# SHDN21-S01-V00-Shutdown.net
KiCad netlist of a schematic drawn in Altium Designer
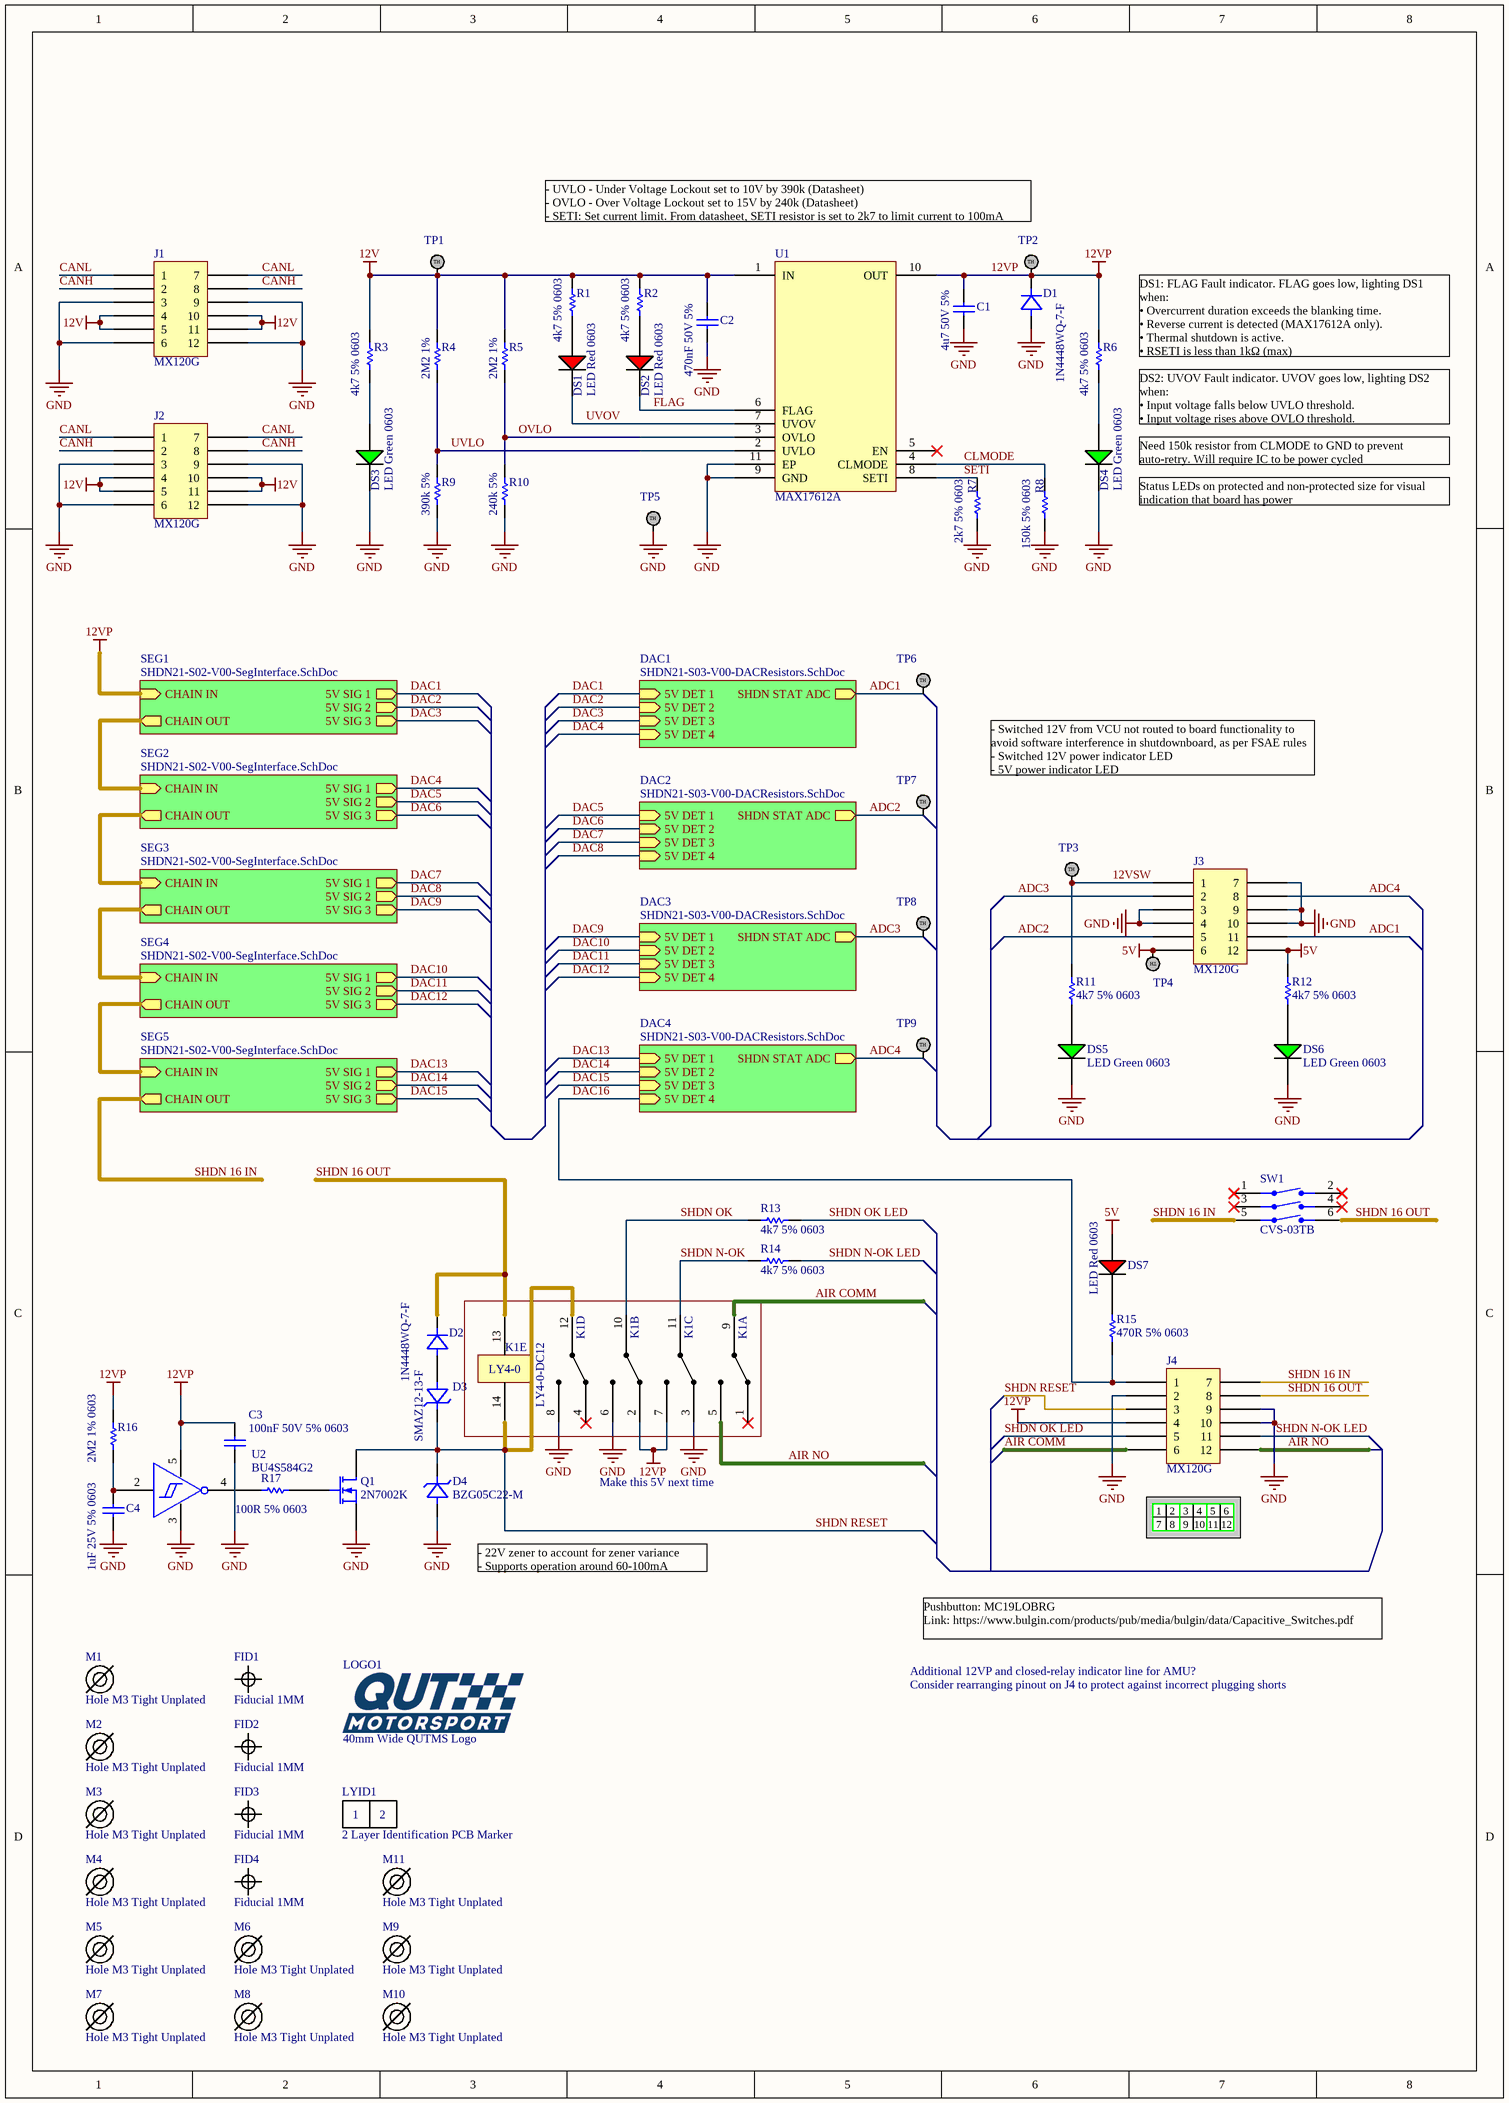
[diagram p0: SHDN21-S01-V00-Shutdown.SchDoc]

(export (version "E")
  (design (tool "Eeschema 10.0.6"))
  (components
    (comp (ref "C1")
      (value "4u7 50V 5%")
      (footprint "Cap_Ceramic_0603")
      (description "Capacitor, Ceramic, SMD, 4u7, 50V, 5%, X7R, 0603")
      (libsource (lib "StandardCapacitors") (part "4u7 50V 5% X7R 0603"))
    )
    (comp (ref "C2")
      (value "470nF 50V 5%")
      (footprint "Cap_Ceramic_0603")
      (description "Capacitor, Ceramic, SMD, 470nF, 50V, 5%, X7R, 0603")
      (libsource (lib "StandardCapacitors") (part "470nF 50V 5% X7R 0603"))
    )
    (comp (ref "C3")
      (value "100nF 50V 5% 0603")
      (footprint "Cap_Ceramic_0603")
      (description "Capacitor, Ceramic, SMD, 100nF, 50V, 5%, X7R, 0603")
      (libsource (lib "StandardCapacitors") (part "100nF 50V 5% X7R 0603"))
    )
    (comp (ref "C4")
      (value "1uF 25V 5% 0603")
      (footprint "Cap_Ceramic_0603")
      (description "Capacitor, Ceramic, SMD, 1uF, 25V, 5%, X7R, 0603")
      (libsource (lib "StandardCapacitors") (part "1uF 25V 5% X7R 0603"))
    )
    (comp (ref "D1")
      (value "1N4448WQ-7-F")
      (footprint "SMA")
      (description "Diode, SMD, 75V, 5%, 250mA, SOD123")
      (fields
        (field (name "MANUFACTURER") "ON Semiconductor / Fairchild")
        (field (name "MANUFACTURER PART NUMBER") "1N914BWS")
      )
      (libsource (lib "QUTMS_DiodeLibrary") (part "1N4448WQ-7-F"))
    )
    (comp (ref "D2")
      (value "1N4448WQ-7-F")
      (footprint "SMA")
      (description "Diode, SMD, 75V, 5%, 250mA, SOD123")
      (fields
        (field (name "MANUFACTURER") "ON Semiconductor / Fairchild")
        (field (name "MANUFACTURER PART NUMBER") "1N914BWS")
      )
      (libsource (lib "QUTMS_DiodeLibrary") (part "1N4448WQ-7-F"))
    )
    (comp (ref "D3")
      (value "SMAZ12-13-F")
      (footprint "SMA")
      (description "Zener Diode 12V 1W ±5% Surface Mount SMA")
      (fields (field (name "MANUFACTURER") "ON Semiconductor") (field (name "MPN") "MM3Z56VB"))
      (libsource (lib "QUTMS_DiodeLibrary") (part "SMAZ12-13-F"))
    )
    (comp (ref "D4")
      (value "BZG05C22-M")
      (footprint "SMA")
      (description "Zener Diodes Uni-direc 40W Pppm SMA (DO-214AC)")
      (libsource (lib "QUTMS_DiodeLibrary") (part "BZG05C22-M"))
    )
    (comp (ref "DS1")
      (value "LED Red 0603")
      (footprint "LED RED 0603")
      (libsource (lib "QUTMS_LEDLibrary") (part "LED Red 0603"))
    )
    (comp (ref "DS2")
      (value "LED Red 0603")
      (footprint "LED RED 0603")
      (libsource (lib "QUTMS_LEDLibrary") (part "LED Red 0603"))
    )
    (comp (ref "DS3")
      (value "LED Green 0603")
      (footprint "LED GREEN 0603")
      (libsource (lib "QUTMS_LEDLibrary") (part "LED Green 0603"))
    )
    (comp (ref "DS4")
      (value "LED Green 0603")
      (footprint "LED GREEN 0603")
      (libsource (lib "QUTMS_LEDLibrary") (part "LED Green 0603"))
    )
    (comp (ref "DS5")
      (value "LED Green 0603")
      (footprint "LED GREEN 0603")
      (libsource (lib "QUTMS_LEDLibrary") (part "LED Green 0603"))
    )
    (comp (ref "DS6")
      (value "LED Green 0603")
      (footprint "LED GREEN 0603")
      (libsource (lib "QUTMS_LEDLibrary") (part "LED Green 0603"))
    )
    (comp (ref "DS7")
      (value "LED Red 0603")
      (footprint "LED RED 0603")
      (libsource (lib "QUTMS_LEDLibrary") (part "LED Red 0603"))
    )
    (comp (ref "FID1")
      (value "Fiducial 1MM")
      (footprint "FIDUCIAL 1MM")
      (libsource (lib "QUTMS_PCBLibrary") (part "Fiducial 1MM"))
    )
    (comp (ref "FID2")
      (value "Fiducial 1MM")
      (footprint "FIDUCIAL 1MM")
      (libsource (lib "QUTMS_PCBLibrary") (part "Fiducial 1MM"))
    )
    (comp (ref "FID3")
      (value "Fiducial 1MM")
      (footprint "FIDUCIAL 1MM")
      (libsource (lib "QUTMS_PCBLibrary") (part "Fiducial 1MM"))
    )
    (comp (ref "FID4")
      (value "Fiducial 1MM")
      (footprint "FIDUCIAL 1MM")
      (libsource (lib "QUTMS_PCBLibrary") (part "Fiducial 1MM"))
    )
    (comp (ref "J1")
      (value "MX120G")
      (footprint "MX120G")
      (description "MX120G with standard connector layout")
      (libsource (lib "QUTMS_MolexLibrary") (part "MX120G"))
    )
    (comp (ref "J2")
      (value "MX120G")
      (footprint "MX120G")
      (description "MX120G with standard connector layout")
      (libsource (lib "QUTMS_MolexLibrary") (part "MX120G"))
    )
    (comp (ref "J3")
      (value "MX120G")
      (footprint "MX120G")
      (description "MX120G with standard connector layout")
      (libsource (lib "QUTMS_MolexLibrary") (part "MX120G"))
    )
    (comp (ref "J4")
      (value "MX120G")
      (footprint "MX120G")
      (description "MX120G with standard connector layout")
      (libsource (lib "QUTMS_MolexLibrary") (part "MX120G"))
    )
    (comp (ref "K1")
      (value "LY4-0-DC12")
      (footprint "LY4-0-DC12")
      (description "RELAY GEN PURPOSE 4PDT 10A 12V Through-hole")
      (libsource (lib "QUTMS_RelayLibrary") (part "LY4-0-DC12_Parts"))
    )
    (comp (ref "LOGO1")
      (value "40mm Wide QUTMS Logo")
      (footprint "QUTMS LOGO 40MM")
      (libsource (lib "QUTMS_PCBLibrary") (part "QUTMS Logo 40mm"))
    )
    (comp (ref "LYID1")
      (value "2 Layer Identification PCB Marker")
      (footprint "LAYER IDENT 2")
      (libsource (lib "QUTMS_PCBLibrary") (part "Layer Identification 2"))
    )
    (comp (ref "M1")
      (value "Hole M3 Tight Unplated")
      (footprint "M3.2 UNPLATED")
      (description "M3.2 Hole, No Plating")
      (libsource (lib "QUTMS_PCBLibrary") (part "Hole M3 Tight Unplated"))
    )
    (comp (ref "M2")
      (value "Hole M3 Tight Unplated")
      (footprint "M3.2 UNPLATED")
      (description "M3.2 Hole, No Plating")
      (libsource (lib "QUTMS_PCBLibrary") (part "Hole M3 Tight Unplated"))
    )
    (comp (ref "M3")
      (value "Hole M3 Tight Unplated")
      (footprint "M3.2 UNPLATED")
      (description "M3.2 Hole, No Plating")
      (libsource (lib "QUTMS_PCBLibrary") (part "Hole M3 Tight Unplated"))
    )
    (comp (ref "M4")
      (value "Hole M3 Tight Unplated")
      (footprint "M3.2 UNPLATED")
      (description "M3.2 Hole, No Plating")
      (libsource (lib "QUTMS_PCBLibrary") (part "Hole M3 Tight Unplated"))
    )
    (comp (ref "M5")
      (value "Hole M3 Tight Unplated")
      (footprint "M3.2 UNPLATED")
      (description "M3.2 Hole, No Plating")
      (libsource (lib "QUTMS_PCBLibrary") (part "Hole M3 Tight Unplated"))
    )
    (comp (ref "M6")
      (value "Hole M3 Tight Unplated")
      (footprint "M3.2 UNPLATED")
      (description "M3.2 Hole, No Plating")
      (libsource (lib "QUTMS_PCBLibrary") (part "Hole M3 Tight Unplated"))
    )
    (comp (ref "M7")
      (value "Hole M3 Tight Unplated")
      (footprint "M3.2 UNPLATED")
      (description "M3.2 Hole, No Plating")
      (libsource (lib "QUTMS_PCBLibrary") (part "Hole M3 Tight Unplated"))
    )
    (comp (ref "M8")
      (value "Hole M3 Tight Unplated")
      (footprint "M3.2 UNPLATED")
      (description "M3.2 Hole, No Plating")
      (libsource (lib "QUTMS_PCBLibrary") (part "Hole M3 Tight Unplated"))
    )
    (comp (ref "M9")
      (value "Hole M3 Tight Unplated")
      (footprint "M3.2 UNPLATED")
      (description "M3.2 Hole, No Plating")
      (libsource (lib "QUTMS_PCBLibrary") (part "Hole M3 Tight Unplated"))
    )
    (comp (ref "M10")
      (value "Hole M3 Tight Unplated")
      (footprint "M3.2 UNPLATED")
      (description "M3.2 Hole, No Plating")
      (libsource (lib "QUTMS_PCBLibrary") (part "Hole M3 Tight Unplated"))
    )
    (comp (ref "M11")
      (value "Hole M3 Tight Unplated")
      (footprint "M3.2 UNPLATED")
      (description "M3.2 Hole, No Plating")
      (libsource (lib "QUTMS_PCBLibrary") (part "Hole M3 Tight Unplated"))
    )
    (comp (ref "Q1")
      (value "2N7002K")
      (footprint "SOT-23-3")
      (description "N-Channel 60V 300mA (Ta) 350mW (Ta) Surface Mount SOT-23 (TO-236AB)")
      (libsource (lib "QUTMS_Transistors") (part "2N7002K"))
    )
    (comp (ref "R1")
      (value "4k7 5% 0603")
      (footprint "Res_ThinFilm_0603")
      (description "Resistor, SMD, 4k7, 0.1W, 5%, 0603")
      (libsource (lib "StandardResistors") (part "4k7 5% 0603"))
    )
    (comp (ref "R2")
      (value "4k7 5% 0603")
      (footprint "Res_ThinFilm_0603")
      (description "Resistor, SMD, 4k7, 0.1W, 5%, 0603")
      (libsource (lib "StandardResistors") (part "4k7 5% 0603"))
    )
    (comp (ref "R3")
      (value "4k7 5% 0603")
      (footprint "Res_ThinFilm_0603")
      (description "Resistor, SMD, 4k7, 0.1W, 5%, 0603")
      (libsource (lib "StandardResistors") (part "4k7 5% 0603"))
    )
    (comp (ref "R4")
      (value "2M2 1%")
      (footprint "Res_ThinFilm_0603")
      (description "Resistor, SMD, 2M2, 0.125W, 1%, 0603")
      (libsource (lib "StandardResistors") (part "2M2 1% 0603"))
    )
    (comp (ref "R5")
      (value "2M2 1%")
      (footprint "Res_ThinFilm_0603")
      (description "Resistor, SMD, 2M2, 0.125W, 1%, 0603")
      (libsource (lib "StandardResistors") (part "2M2 1% 0603"))
    )
    (comp (ref "R6")
      (value "4k7 5% 0603")
      (footprint "Res_ThinFilm_0603")
      (description "Resistor, SMD, 4k7, 0.1W, 5%, 0603")
      (libsource (lib "StandardResistors") (part "4k7 5% 0603"))
    )
    (comp (ref "R7")
      (value "2k7 5% 0603")
      (footprint "Res_ThinFilm_0603")
      (description "Resistor, SMD, 2k7, 0.1W, 5%, 0603")
      (libsource (lib "StandardResistors") (part "2k7 5% 0603"))
    )
    (comp (ref "R8")
      (value "150k 5% 0603")
      (footprint "Res_ThinFilm_0603")
      (description "Resistor, SMD, 150k, 0.1W, 5%, 0603")
      (libsource (lib "StandardResistors") (part "150k 5%, 0603"))
    )
    (comp (ref "R9")
      (value "390k 5%")
      (footprint "Res_ThinFilm_0603")
      (description "Resistor, SMD, 390k, 0.1W, 5%, 0603")
      (libsource (lib "StandardResistors") (part "390k 5% 0603"))
    )
    (comp (ref "R10")
      (value "240k 5%")
      (footprint "Res_ThinFilm_0603")
      (description "Resistor, SMD, 240k, 0.1W, 5%, 0603")
      (libsource (lib "StandardResistors") (part "240k 5% 0603"))
    )
    (comp (ref "R11")
      (value "4k7 5% 0603")
      (footprint "Res_ThinFilm_0603")
      (description "Resistor, SMD, 4k7, 0.1W, 5%, 0603")
      (libsource (lib "StandardResistors") (part "4k7 5% 0603"))
    )
    (comp (ref "R12")
      (value "4k7 5% 0603")
      (footprint "Res_ThinFilm_0603")
      (description "Resistor, SMD, 4k7, 0.1W, 5%, 0603")
      (libsource (lib "StandardResistors") (part "4k7 5% 0603"))
    )
    (comp (ref "R13")
      (value "4k7 5% 0603")
      (footprint "Res_ThinFilm_0603")
      (description "Resistor, SMD, 4k7, 0.1W, 5%, 0603")
      (libsource (lib "StandardResistors") (part "4k7 5% 0603"))
    )
    (comp (ref "R14")
      (value "4k7 5% 0603")
      (footprint "Res_ThinFilm_0603")
      (description "Resistor, SMD, 4k7, 0.1W, 5%, 0603")
      (libsource (lib "StandardResistors") (part "4k7 5% 0603"))
    )
    (comp (ref "R15")
      (value "470R 5% 0603")
      (footprint "Res_ThinFilm_0603")
      (description "Resistor, SMD, 470R, 0.1W, 5%, 0603")
      (libsource (lib "StandardResistors") (part "470R 5% 0603"))
    )
    (comp (ref "R16")
      (value "2M2 1% 0603")
      (footprint "Res_ThinFilm_0603")
      (description "Resistor, SMD, 2M2, 0.125W, 1%, 0603")
      (libsource (lib "StandardResistors") (part "2M2 1% 0603"))
    )
    (comp (ref "R17")
      (value "100R 5% 0603")
      (footprint "Res_ThinFilm_0603")
      (description "Resistor, SMD, 100R, 0.1W, 5%, 0603")
      (libsource (lib "StandardResistors") (part "100R 5%, 0603"))
    )
    (comp (ref "SW1")
      (value "CVS-03TB")
      (footprint "CVS-03TB")
      (description "SWITCH SLIDE DIP SPST 100MA 6V")
      (libsource (lib "QUTMS_SwitchLibrary") (part "CVS-03TB"))
    )
    (comp (ref "TP1")
      (value "TestPoint")
      (footprint "TestPoint")
      (libsource (lib "StandardTest") (part "TestPoint"))
    )
    (comp (ref "TP2")
      (value "TestPoint")
      (footprint "TestPoint")
      (libsource (lib "StandardTest") (part "TestPoint"))
    )
    (comp (ref "TP3")
      (value "TestPoint")
      (footprint "TestPoint")
      (libsource (lib "StandardTest") (part "TestPoint"))
    )
    (comp (ref "TP4")
      (value "TestPoint")
      (footprint "TestPoint")
      (libsource (lib "StandardTest") (part "TestPoint"))
    )
    (comp (ref "TP5")
      (value "TestPoint")
      (footprint "TestPoint")
      (libsource (lib "StandardTest") (part "TestPoint"))
    )
    (comp (ref "TP6")
      (value "TestPoint")
      (footprint "TestPoint")
      (libsource (lib "StandardTest") (part "TestPoint"))
    )
    (comp (ref "TP7")
      (value "TestPoint")
      (footprint "TestPoint")
      (libsource (lib "StandardTest") (part "TestPoint"))
    )
    (comp (ref "TP8")
      (value "TestPoint")
      (footprint "TestPoint")
      (libsource (lib "StandardTest") (part "TestPoint"))
    )
    (comp (ref "TP9")
      (value "TestPoint")
      (footprint "TestPoint")
      (libsource (lib "StandardTest") (part "TestPoint"))
    )
    (comp (ref "U1")
      (value "MAX17612A")
      (footprint "10-Pin TDFN EP")
      (libsource (lib "QUTMS_IntegratedCircuitLibrary") (part "MAX17612A"))
    )
    (comp (ref "U2")
      (value "BU4S584G2")
      (footprint "SSOP5")
      (description "IC INVERTER SCHMITT 1CH 5SSOP")
      (libsource (lib "QUTMS_LogicLibrary") (part "BU4S584G2"))
    )
  )
  (nets
    (net (code "1") (name "/12VSW") (class "Default")
      (node (ref "J3") (pin "1") (pinfunction "1_1") (pintype "passive"))
      (node (ref "R11") (pin "2") (pinfunction "2_2") (pintype "passive"))
      (node (ref "TP3") (pin "1") (pinfunction "1_1") (pintype "passive"))
    )
    (net (code "2") (name "/ADC1") (class "Default")
      (node (ref "J3") (pin "11") (pinfunction "11_11") (pintype "passive"))
      (node (ref "TP6") (pin "1") (pinfunction "1_1") (pintype "passive"))
    )
    (net (code "3") (name "/ADC2") (class "Default")
      (node (ref "J3") (pin "5") (pinfunction "5_5") (pintype "passive"))
      (node (ref "TP7") (pin "1") (pinfunction "1_1") (pintype "passive"))
    )
    (net (code "4") (name "/ADC3") (class "Default")
      (node (ref "J3") (pin "2") (pinfunction "2_2") (pintype "passive"))
      (node (ref "TP8") (pin "1") (pinfunction "1_1") (pintype "passive"))
    )
    (net (code "5") (name "/ADC4") (class "Default")
      (node (ref "J3") (pin "8") (pinfunction "8_8") (pintype "passive"))
      (node (ref "TP9") (pin "1") (pinfunction "1_1") (pintype "passive"))
    )
    (net (code "6") (name "/AIR COMM") (class "Default")
      (node (ref "J4") (pin "6") (pinfunction "6_6") (pintype "passive"))
      (node (ref "K1") (pin "9") (pinfunction "9_9") (pintype "passive"))
    )
    (net (code "7") (name "/AIR NO") (class "Default")
      (node (ref "J4") (pin "12") (pinfunction "12_12") (pintype "passive"))
      (node (ref "K1") (pin "5") (pinfunction "5_5") (pintype "passive"))
    )
    (net (code "8") (name "/CANH") (class "Default")
      (node (ref "J1") (pin "2") (pinfunction "2_2") (pintype "passive"))
      (node (ref "J1") (pin "8") (pinfunction "8_8") (pintype "passive"))
      (node (ref "J2") (pin "2") (pinfunction "2_2") (pintype "passive"))
      (node (ref "J2") (pin "8") (pinfunction "8_8") (pintype "passive"))
    )
    (net (code "9") (name "/CANL") (class "Default")
      (node (ref "J1") (pin "1") (pinfunction "1_1") (pintype "passive"))
      (node (ref "J1") (pin "7") (pinfunction "7_7") (pintype "passive"))
      (node (ref "J2") (pin "1") (pinfunction "1_1") (pintype "passive"))
      (node (ref "J2") (pin "7") (pinfunction "7_7") (pintype "passive"))
    )
    (net (code "14") (name "/CLMODE") (class "Default")
      (node (ref "R8") (pin "2") (pinfunction "2_2") (pintype "passive"))
      (node (ref "U1") (pin "4") (pinfunction "CLMODE_4") (pintype "passive"))
    )
    (net (code "30") (name "/DAC16") (class "Default")
      (node (ref "J4") (pin "1") (pinfunction "1_1") (pintype "passive"))
      (node (ref "R15") (pin "1") (pinfunction "1_1") (pintype "passive"))
    )
    (net (code "31") (name "/FLAG") (class "Default")
      (node (ref "DS2") (pin "2") (pinfunction "C_2") (pintype "passive"))
      (node (ref "U1") (pin "6") (pinfunction "FLAG_6") (pintype "passive"))
    )
    (net (code "32") (name "/OVLO") (class "Default")
      (node (ref "R10") (pin "2") (pinfunction "2_2") (pintype "passive"))
      (node (ref "R5") (pin "1") (pinfunction "1_1") (pintype "passive"))
      (node (ref "U1") (pin "3") (pinfunction "OVLO_3") (pintype "passive"))
    )
    (net (code "33") (name "/SETI") (class "Default")
      (node (ref "R7") (pin "1") (pinfunction "1_1") (pintype "passive"))
      (node (ref "U1") (pin "8") (pinfunction "SETI_8") (pintype "passive"))
    )
    (net (code "34") (name "/SHDN 16 IN") (class "Default")
      (node (ref "J4") (pin "7") (pinfunction "7_7") (pintype "passive"))
      (node (ref "SW1") (pin "5") (pinfunction "5_5") (pintype "passive"))
    )
    (net (code "35") (name "/SHDN 16 OUT") (class "Default")
      (node (ref "D2") (pin "K") (pinfunction "Cathode_K") (pintype "passive"))
      (node (ref "J4") (pin "8") (pinfunction "8_8") (pintype "passive"))
      (node (ref "K1") (pin "13") (pinfunction "13_13") (pintype "passive"))
      (node (ref "SW1") (pin "6") (pinfunction "6_6") (pintype "passive"))
    )
    (net (code "36") (name "/SHDN N-OK") (class "Default")
      (node (ref "K1") (pin "11") (pinfunction "11_11") (pintype "passive"))
      (node (ref "R14") (pin "1") (pinfunction "1_1") (pintype "passive"))
    )
    (net (code "37") (name "/SHDN N-OK LED") (class "Default")
      (node (ref "J4") (pin "11") (pinfunction "11_11") (pintype "passive"))
      (node (ref "R14") (pin "2") (pinfunction "2_2") (pintype "passive"))
    )
    (net (code "38") (name "/SHDN OK") (class "Default")
      (node (ref "K1") (pin "10") (pinfunction "10_10") (pintype "passive"))
      (node (ref "R13") (pin "1") (pinfunction "1_1") (pintype "passive"))
    )
    (net (code "39") (name "/SHDN OK LED") (class "Default")
      (node (ref "J4") (pin "5") (pinfunction "5_5") (pintype "passive"))
      (node (ref "R13") (pin "2") (pinfunction "2_2") (pintype "passive"))
    )
    (net (code "40") (name "/SHDN RESET") (class "Default")
      (node (ref "D3") (pin "K") (pinfunction "Cathode_K") (pintype "passive"))
      (node (ref "D4") (pin "K") (pinfunction "Cathode_K") (pintype "passive"))
      (node (ref "J4") (pin "3") (pinfunction "3_3") (pintype "passive"))
      (node (ref "K1") (pin "12") (pinfunction "12_12") (pintype "passive"))
      (node (ref "K1") (pin "14") (pinfunction "14_14") (pintype "passive"))
      (node (ref "Q1") (pin "D") (pinfunction "D_D") (pintype "passive"))
    )
    (net (code "41") (name "/UVLO") (class "Default")
      (node (ref "R4") (pin "1") (pinfunction "1_1") (pintype "passive"))
      (node (ref "R9") (pin "2") (pinfunction "2_2") (pintype "passive"))
      (node (ref "U1") (pin "2") (pinfunction "UVLO_2") (pintype "passive"))
    )
    (net (code "42") (name "/UVOV") (class "Default")
      (node (ref "DS1") (pin "2") (pinfunction "C_2") (pintype "passive"))
      (node (ref "U1") (pin "7") (pinfunction "UVOV_7") (pintype "passive"))
    )
    (net (code "43") (name "5V") (class "Default")
      (node (ref "DS7") (pin "1") (pinfunction "A_1") (pintype "passive"))
      (node (ref "J3") (pin "12") (pinfunction "12_12") (pintype "passive"))
      (node (ref "J3") (pin "6") (pinfunction "6_6") (pintype "passive"))
      (node (ref "R12") (pin "2") (pinfunction "2_2") (pintype "passive"))
      (node (ref "TP4") (pin "1") (pinfunction "1_1") (pintype "passive"))
    )
    (net (code "44") (name "12V") (class "Default")
      (node (ref "C2") (pin "2") (pinfunction "2_2") (pintype "passive"))
      (node (ref "J1") (pin "10") (pinfunction "10_10") (pintype "passive"))
      (node (ref "J1") (pin "11") (pinfunction "11_11") (pintype "passive"))
      (node (ref "J1") (pin "4") (pinfunction "4_4") (pintype "passive"))
      (node (ref "J1") (pin "5") (pinfunction "5_5") (pintype "passive"))
      (node (ref "J2") (pin "10") (pinfunction "10_10") (pintype "passive"))
      (node (ref "J2") (pin "11") (pinfunction "11_11") (pintype "passive"))
      (node (ref "J2") (pin "4") (pinfunction "4_4") (pintype "passive"))
      (node (ref "J2") (pin "5") (pinfunction "5_5") (pintype "passive"))
      (node (ref "R1") (pin "2") (pinfunction "2_2") (pintype "passive"))
      (node (ref "R2") (pin "2") (pinfunction "2_2") (pintype "passive"))
      (node (ref "R3") (pin "2") (pinfunction "2_2") (pintype "passive"))
      (node (ref "R4") (pin "2") (pinfunction "2_2") (pintype "passive"))
      (node (ref "R5") (pin "2") (pinfunction "2_2") (pintype "passive"))
      (node (ref "TP1") (pin "1") (pinfunction "1_1") (pintype "passive"))
      (node (ref "U1") (pin "1") (pinfunction "IN_1") (pintype "passive"))
    )
    (net (code "45") (name "12VP") (class "Default")
      (node (ref "C1") (pin "2") (pinfunction "2_2") (pintype "passive"))
      (node (ref "C3") (pin "1") (pinfunction "1_1") (pintype "passive"))
      (node (ref "D1") (pin "K") (pinfunction "Cathode_K") (pintype "passive"))
      (node (ref "J4") (pin "4") (pinfunction "4_4") (pintype "passive"))
      (node (ref "K1") (pin "2") (pinfunction "2_2") (pintype "passive"))
      (node (ref "K1") (pin "7") (pinfunction "7_7") (pintype "passive"))
      (node (ref "R16") (pin "2") (pinfunction "2_2") (pintype "passive"))
      (node (ref "R6") (pin "2") (pinfunction "2_2") (pintype "passive"))
      (node (ref "TP2") (pin "1") (pinfunction "1_1") (pintype "passive"))
      (node (ref "U1") (pin "10") (pinfunction "OUT_10") (pintype "passive"))
      (node (ref "U2") (pin "5") (pinfunction "VDD_5") (pintype "passive"))
    )
    (net (code "46") (name "GND") (class "Default")
      (node (ref "C1") (pin "1") (pinfunction "1_1") (pintype "passive"))
      (node (ref "C2") (pin "1") (pinfunction "1_1") (pintype "passive"))
      (node (ref "C3") (pin "2") (pinfunction "2_2") (pintype "passive"))
      (node (ref "C4") (pin "1") (pinfunction "1_1") (pintype "passive"))
      (node (ref "D1") (pin "A") (pinfunction "Anode_A") (pintype "passive"))
      (node (ref "D4") (pin "A") (pinfunction "Anode_A") (pintype "passive"))
      (node (ref "DS3") (pin "2") (pinfunction "C_2") (pintype "passive"))
      (node (ref "DS4") (pin "2") (pinfunction "C_2") (pintype "passive"))
      (node (ref "DS5") (pin "2") (pinfunction "C_2") (pintype "passive"))
      (node (ref "DS6") (pin "2") (pinfunction "C_2") (pintype "passive"))
      (node (ref "J1") (pin "12") (pinfunction "12_12") (pintype "passive"))
      (node (ref "J1") (pin "3") (pinfunction "3_3") (pintype "passive"))
      (node (ref "J1") (pin "6") (pinfunction "6_6") (pintype "passive"))
      (node (ref "J1") (pin "9") (pinfunction "9_9") (pintype "passive"))
      (node (ref "J2") (pin "12") (pinfunction "12_12") (pintype "passive"))
      (node (ref "J2") (pin "3") (pinfunction "3_3") (pintype "passive"))
      (node (ref "J2") (pin "6") (pinfunction "6_6") (pintype "passive"))
      (node (ref "J2") (pin "9") (pinfunction "9_9") (pintype "passive"))
      (node (ref "J3") (pin "10") (pinfunction "10_10") (pintype "passive"))
      (node (ref "J3") (pin "3") (pinfunction "3_3") (pintype "passive"))
      (node (ref "J3") (pin "4") (pinfunction "4_4") (pintype "passive"))
      (node (ref "J3") (pin "7") (pinfunction "7_7") (pintype "passive"))
      (node (ref "J3") (pin "9") (pinfunction "9_9") (pintype "passive"))
      (node (ref "J4") (pin "10") (pinfunction "10_10") (pintype "passive"))
      (node (ref "J4") (pin "2") (pinfunction "2_2") (pintype "passive"))
      (node (ref "J4") (pin "9") (pinfunction "9_9") (pintype "passive"))
      (node (ref "K1") (pin "3") (pinfunction "3_3") (pintype "passive"))
      (node (ref "K1") (pin "6") (pinfunction "6_6") (pintype "passive"))
      (node (ref "K1") (pin "8") (pinfunction "8_8") (pintype "passive"))
      (node (ref "Q1") (pin "S") (pinfunction "S_S") (pintype "passive"))
      (node (ref "R10") (pin "1") (pinfunction "1_1") (pintype "passive"))
      (node (ref "R7") (pin "2") (pinfunction "2_2") (pintype "passive"))
      (node (ref "R8") (pin "1") (pinfunction "1_1") (pintype "passive"))
      (node (ref "R9") (pin "1") (pinfunction "1_1") (pintype "passive"))
      (node (ref "TP5") (pin "1") (pinfunction "1_1") (pintype "passive"))
      (node (ref "U1") (pin "11") (pinfunction "EP_11") (pintype "passive"))
      (node (ref "U1") (pin "9") (pinfunction "GND_9") (pintype "passive"))
      (node (ref "U2") (pin "3") (pinfunction "VSS_3") (pintype "passive"))
    )
    (net (code "47") (name "Net-(D2-Anode)") (class "Default")
      (node (ref "D2") (pin "A") (pinfunction "Anode_A") (pintype "passive"))
      (node (ref "D3") (pin "A") (pinfunction "Anode_A") (pintype "passive"))
    )
    (net (code "48") (name "Net-(DS1-A)") (class "Default")
      (node (ref "DS1") (pin "1") (pinfunction "A_1") (pintype "passive"))
      (node (ref "R1") (pin "1") (pinfunction "1_1") (pintype "passive"))
    )
    (net (code "49") (name "Net-(DS2-A)") (class "Default")
      (node (ref "DS2") (pin "1") (pinfunction "A_1") (pintype "passive"))
      (node (ref "R2") (pin "1") (pinfunction "1_1") (pintype "passive"))
    )
    (net (code "50") (name "Net-(DS3-A)") (class "Default")
      (node (ref "DS3") (pin "1") (pinfunction "A_1") (pintype "passive"))
      (node (ref "R3") (pin "1") (pinfunction "1_1") (pintype "passive"))
    )
    (net (code "51") (name "Net-(DS4-A)") (class "Default")
      (node (ref "DS4") (pin "1") (pinfunction "A_1") (pintype "passive"))
      (node (ref "R6") (pin "1") (pinfunction "1_1") (pintype "passive"))
    )
    (net (code "52") (name "Net-(DS5-A)") (class "Default")
      (node (ref "DS5") (pin "1") (pinfunction "A_1") (pintype "passive"))
      (node (ref "R11") (pin "1") (pinfunction "1_1") (pintype "passive"))
    )
    (net (code "53") (name "Net-(DS6-A)") (class "Default")
      (node (ref "DS6") (pin "1") (pinfunction "A_1") (pintype "passive"))
      (node (ref "R12") (pin "1") (pinfunction "1_1") (pintype "passive"))
    )
    (net (code "54") (name "Net-(DS7-C)") (class "Default")
      (node (ref "DS7") (pin "2") (pinfunction "C_2") (pintype "passive"))
      (node (ref "R15") (pin "2") (pinfunction "2_2") (pintype "passive"))
    )
    (net (code "55") (name "Net-(Q1-PadG)") (class "Default")
      (node (ref "Q1") (pin "G") (pinfunction "G_G") (pintype "passive"))
      (node (ref "R17") (pin "2") (pinfunction "2_2") (pintype "passive"))
    )
    (net (code "56") (name "Net-(U2-A)") (class "Default")
      (node (ref "C4") (pin "2") (pinfunction "2_2") (pintype "passive"))
      (node (ref "R16") (pin "1") (pinfunction "1_1") (pintype "passive"))
      (node (ref "U2") (pin "2") (pinfunction "A_2") (pintype "passive"))
    )
    (net (code "57") (name "Net-(U2-Y)") (class "Default")
      (node (ref "R17") (pin "1") (pinfunction "1_1") (pintype "passive"))
      (node (ref "U2") (pin "4") (pinfunction "Y_4") (pintype "passive"))
    )
    (net (code "58") (name "unconnected-(K1-Pad1)") (class "Default")
      (node (ref "K1") (pin "1") (pinfunction "1_1") (pintype "passive+no_connect"))
    )
    (net (code "59") (name "unconnected-(K1-Pad4)") (class "Default")
      (node (ref "K1") (pin "4") (pinfunction "4_4") (pintype "passive+no_connect"))
    )
    (net (code "60") (name "unconnected-(SW1-Pad1)") (class "Default")
      (node (ref "SW1") (pin "1") (pinfunction "1_1") (pintype "passive+no_connect"))
    )
    (net (code "61") (name "unconnected-(SW1-Pad2)") (class "Default")
      (node (ref "SW1") (pin "2") (pinfunction "2_2") (pintype "passive+no_connect"))
    )
    (net (code "62") (name "unconnected-(SW1-Pad3)") (class "Default")
      (node (ref "SW1") (pin "3") (pinfunction "3_3") (pintype "passive+no_connect"))
    )
    (net (code "63") (name "unconnected-(SW1-Pad4)") (class "Default")
      (node (ref "SW1") (pin "4") (pinfunction "4_4") (pintype "passive+no_connect"))
    )
    (net (code "64") (name "unconnected-(U1-EN-Pad5)") (class "Default")
      (node (ref "U1") (pin "5") (pinfunction "EN_5") (pintype "passive+no_connect"))
    )
  )
)
